# Sheet2-PICO-IMU_V2.net
KiCad netlist of a schematic drawn in Altium Designer
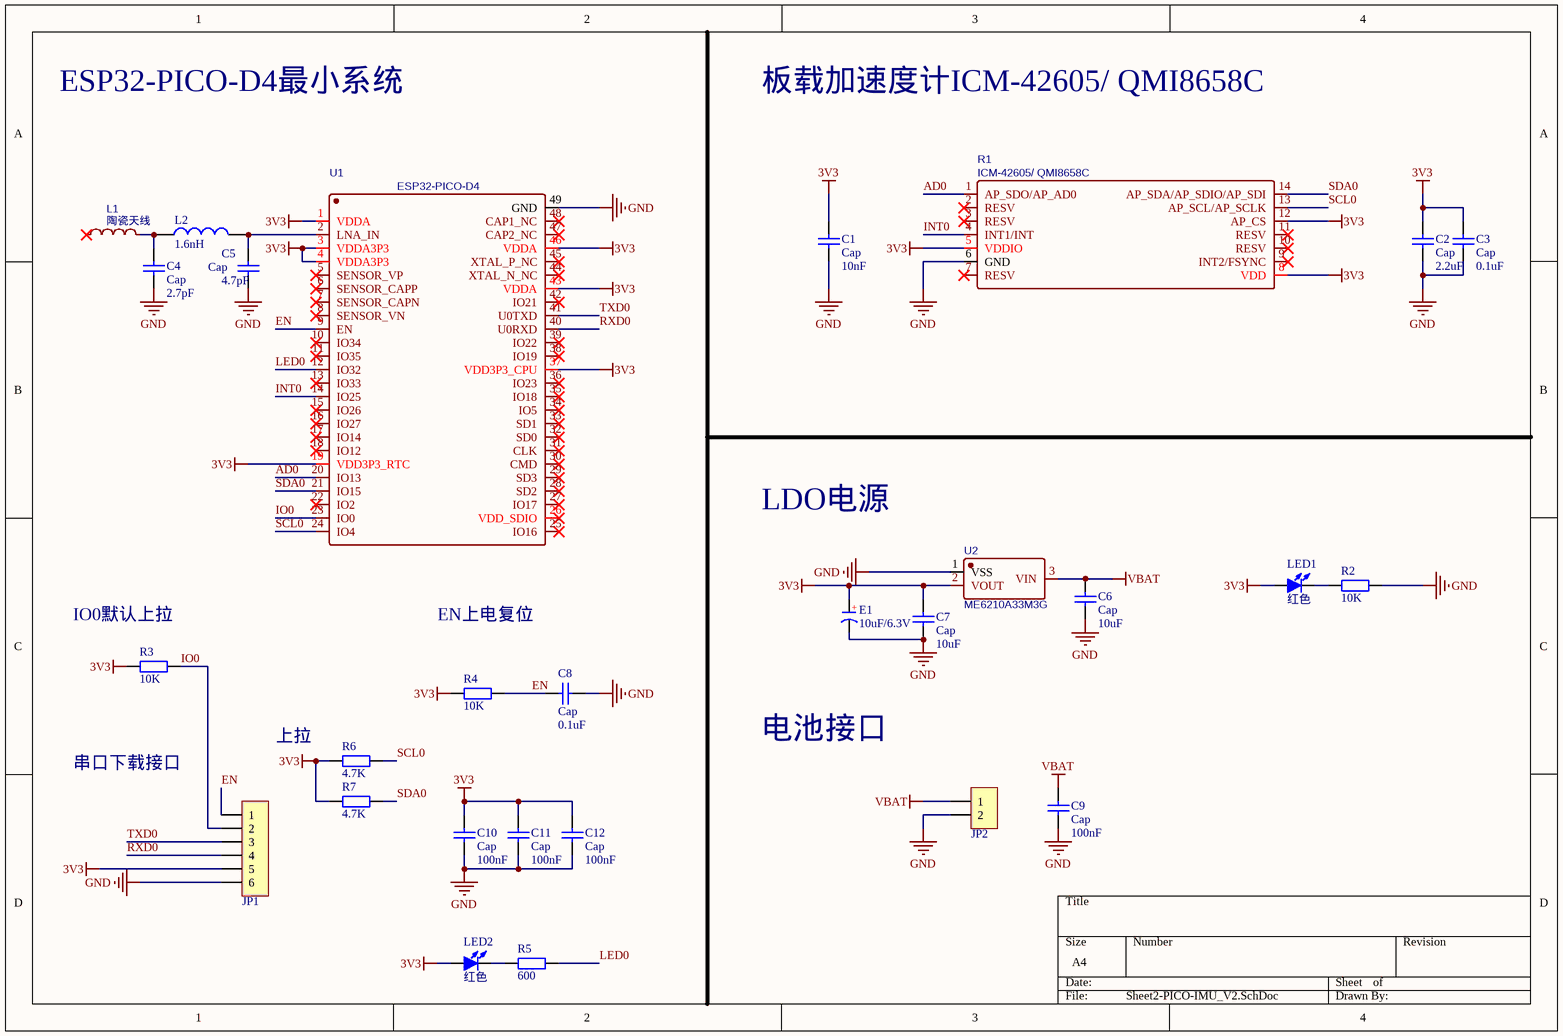
[diagram p0: Sheet2-PICO-IMU_V2.SchDoc]

(export (version "E")
  (design (tool "Eeschema 10.0.6"))
  (components
    (comp (ref "C1")
      (value "Cap")
      (footprint "C 0402_L")
      (description "Capacitor")
      (fields (field (name "ALTIUM_VALUE") "10nF") (field (name "PUBLISHER") "Altium Limited"))
      (libsource (lib "Miscellaneous Devices") (part "Cap"))
    )
    (comp (ref "C2")
      (value "Cap")
      (footprint "C 0402_L")
      (description "Capacitor")
      (fields (field (name "ALTIUM_VALUE") "2.2uF") (field (name "PUBLISHER") "Altium Limited"))
      (libsource (lib "Miscellaneous Devices") (part "Cap"))
    )
    (comp (ref "C3")
      (value "Cap")
      (footprint "C 0402_L")
      (description "Capacitor")
      (fields (field (name "ALTIUM_VALUE") "0.1uF") (field (name "PUBLISHER") "Altium Limited"))
      (libsource (lib "Miscellaneous Devices") (part "Cap"))
    )
    (comp (ref "C4")
      (value "Cap")
      (footprint "C 0402_L")
      (description "Capacitor")
      (fields (field (name "ALTIUM_VALUE") "2.7pF") (field (name "PUBLISHER") "Altium Limited"))
      (libsource (lib "Miscellaneous Devices") (part "Cap"))
    )
    (comp (ref "C5")
      (value "Cap")
      (footprint "C 0402_L")
      (description "Capacitor")
      (fields (field (name "ALTIUM_VALUE") "4.7pF") (field (name "PUBLISHER") "Altium Limited"))
      (libsource (lib "Miscellaneous Devices") (part "Cap"))
    )
    (comp (ref "C6")
      (value "Cap")
      (footprint "C 0402_L")
      (description "Capacitor")
      (fields (field (name "ALTIUM_VALUE") "10uF") (field (name "PUBLISHER") "Altium Limited"))
      (libsource (lib "Miscellaneous Devices") (part "Cap"))
    )
    (comp (ref "C7")
      (value "Cap")
      (footprint "C 0402_L")
      (description "Capacitor")
      (fields (field (name "ALTIUM_VALUE") "10uF") (field (name "PUBLISHER") "Altium Limited"))
      (libsource (lib "Miscellaneous Devices") (part "Cap"))
    )
    (comp (ref "C8")
      (value "Cap")
      (footprint "C 0402_L")
      (description "Capacitor")
      (fields (field (name "ALTIUM_VALUE") "0.1uF") (field (name "PUBLISHER") "Altium Limited"))
      (libsource (lib "Miscellaneous Devices") (part "Cap"))
    )
    (comp (ref "C9")
      (value "Cap")
      (footprint "C 0402_L")
      (description "Capacitor")
      (fields (field (name "ALTIUM_VALUE") "100nF") (field (name "PUBLISHER") "Altium Limited"))
      (libsource (lib "Miscellaneous Devices") (part "Cap"))
    )
    (comp (ref "C10")
      (value "Cap")
      (footprint "C 0402_L")
      (description "Capacitor")
      (fields (field (name "ALTIUM_VALUE") "100nF") (field (name "PUBLISHER") "Altium Limited"))
      (libsource (lib "Miscellaneous Devices") (part "Cap"))
    )
    (comp (ref "C11")
      (value "Cap")
      (footprint "C 0402_L")
      (description "Capacitor")
      (fields (field (name "ALTIUM_VALUE") "100nF") (field (name "PUBLISHER") "Altium Limited"))
      (libsource (lib "Miscellaneous Devices") (part "Cap"))
    )
    (comp (ref "C12")
      (value "Cap")
      (footprint "C 0402_L")
      (description "Capacitor")
      (fields (field (name "ALTIUM_VALUE") "100nF") (field (name "PUBLISHER") "Altium Limited"))
      (libsource (lib "Miscellaneous Devices") (part "Cap"))
    )
    (comp (ref "E1")
      (value "10uF/6.3V")
      (footprint "CD S(2012)")
      (description "贴片钽电容")
      (fields (field (name "版权归属") "源创客"))
      (libsource (lib "Basic_Integrated_Library") (part "C-CD"))
    )
    (comp (ref "JP1")
      (value "HDR-1X6")
      (footprint "debug")
      (description "6P接插件")
      (fields (field (name "版权归属") "源创客"))
      (libsource (lib "Basic_Integrated_Library") (part "Header 6"))
    )
    (comp (ref "JP2")
      (value "HDR-1X2")
      (footprint "电池焊接口")
      (description "2P接插件")
      (fields (field (name "版权归属") "源创客"))
      (libsource (lib "Basic_Integrated_Library") (part "Header 2"))
    )
    (comp (ref "L1")
      (value "陶瓷天线")
      (footprint "Huaxin")
      (fields
        (field (name "BOM_SUPPLIER PART") "C127620")
        (field (name "BOM_MANUFACTURER PART") "RFECA3216060A1T")
        (field (name "CONTRIBUTOR") "LCSC")
      )
      (libsource (lib "altium-import") (part "root_0_Huaxin_"))
    )
    (comp (ref "L2")
      (value "1.6nH")
      (footprint "L 0402")
      (description "小功率贴片电感")
      (fields (field (name "版权归属") "源创客"))
      (libsource (lib "Basic_Integrated_Library") (part "L"))
    )
    (comp (ref "LED1")
      (value "红色")
      (footprint "LED 0805G")
      (description "贴片LED")
      (fields (field (name "版权归属") "源创客"))
      (libsource (lib "Basic_Integrated_Library") (part "LED-SMD"))
    )
    (comp (ref "LED2")
      (value "红色")
      (footprint "LED 0805G")
      (description "贴片LED")
      (fields (field (name "版权归属") "源创客"))
      (libsource (lib "Basic_Integrated_Library") (part "LED-SMD"))
    )
    (comp (ref "R1")
      (value "ICM-42605/ QMI8658C")
      (footprint "ICM-42605")
      (fields
        (field (name "BOM_SUPPLIER PART") "C2655099")
        (field (name "BOM_MANUFACTURER PART") "ICM-42605")
        (field (name "CONTRIBUTOR") "LCSC")
      )
      (libsource (lib "altium-import") (part "root_0_ICM-42605_"))
    )
    (comp (ref "R2")
      (value "10K")
      (footprint "R 0402_L")
      (description "贴片电阻")
      (fields (field (name "版权归属") "源创客"))
      (libsource (lib "Basic_Integrated_Library") (part "R"))
    )
    (comp (ref "R3")
      (value "10K")
      (footprint "R 0402_L")
      (description "贴片电阻")
      (fields (field (name "版权归属") "源创客"))
      (libsource (lib "Basic_Integrated_Library") (part "R"))
    )
    (comp (ref "R4")
      (value "10K")
      (footprint "R 0402_L")
      (description "贴片电阻")
      (fields (field (name "版权归属") "源创客"))
      (libsource (lib "Basic_Integrated_Library") (part "R"))
    )
    (comp (ref "R5")
      (value "600")
      (footprint "R 0402_L")
      (description "贴片电阻")
      (fields (field (name "版权归属") "源创客"))
      (libsource (lib "Basic_Integrated_Library") (part "R"))
    )
    (comp (ref "R6")
      (value "4.7K")
      (footprint "R 0402_L")
      (description "贴片电阻")
      (fields (field (name "版权归属") "源创客"))
      (libsource (lib "Basic_Integrated_Library") (part "R"))
    )
    (comp (ref "R7")
      (value "4.7K")
      (footprint "R 0402_L")
      (description "贴片电阻")
      (fields (field (name "版权归属") "源创客"))
      (libsource (lib "Basic_Integrated_Library") (part "R"))
    )
    (comp (ref "U1")
      (value "ESP32-PICO-D4")
      (footprint "ESP32-PICO-D4")
      (fields (field (name "BOM_SUPPLIER PART") "C193707") (field (name "CONTRIBUTOR") "LCSC"))
      (libsource (lib "altium-import") (part "root_0_ESP32-PICO-D4_"))
    )
    (comp (ref "U2")
      (value "ME6210A33M3G")
      (footprint "ME6210A33M3G")
      (fields (field (name "BOM_SUPPLIER PART") "C236680") (field (name "CONTRIBUTOR") "LCSC"))
      (libsource (lib "altium-import") (part "root_0_ME6210A33M3G_"))
    )
  )
  (nets
    (net (code "1") (name "/AD0") (class "Default")
      (node (ref "R1") (pin "1") (pinfunction "AP_SDO/AP_AD0_1") (pintype "passive"))
      (node (ref "U1") (pin "20") (pinfunction "IO13_20") (pintype "passive"))
    )
    (net (code "2") (name "/EN") (class "Default")
      (node (ref "C8") (pin "2") (pinfunction "2_2") (pintype "passive"))
      (node (ref "JP1") (pin "1") (pinfunction "1_1") (pintype "passive"))
      (node (ref "R4") (pin "2") (pinfunction "2_2") (pintype "passive"))
      (node (ref "U1") (pin "9") (pinfunction "EN_9") (pintype "passive"))
    )
    (net (code "3") (name "/INT0") (class "Default")
      (node (ref "R1") (pin "4") (pinfunction "INT1/INT_4") (pintype "passive"))
      (node (ref "U1") (pin "14") (pinfunction "IO25_14") (pintype "passive"))
    )
    (net (code "4") (name "/IO0") (class "Default")
      (node (ref "JP1") (pin "2") (pinfunction "2_2") (pintype "passive"))
      (node (ref "R3") (pin "2") (pinfunction "2_2") (pintype "passive"))
      (node (ref "U1") (pin "23") (pinfunction "IO0_23") (pintype "passive"))
    )
    (net (code "5") (name "/LED0") (class "Default")
      (node (ref "R5") (pin "2") (pinfunction "2_2") (pintype "passive"))
      (node (ref "U1") (pin "12") (pinfunction "IO32_12") (pintype "passive"))
    )
    (net (code "6") (name "/RXD0") (class "Default")
      (node (ref "JP1") (pin "4") (pinfunction "4_4") (pintype "passive"))
      (node (ref "U1") (pin "40") (pinfunction "U0RXD_40") (pintype "passive"))
    )
    (net (code "7") (name "/SCL0") (class "Default")
      (node (ref "R1") (pin "13") (pinfunction "AP_SCL/AP_SCLK_13") (pintype "passive"))
      (node (ref "R6") (pin "2") (pinfunction "2_2") (pintype "passive"))
      (node (ref "U1") (pin "24") (pinfunction "IO4_24") (pintype "passive"))
    )
    (net (code "8") (name "/SDA0") (class "Default")
      (node (ref "R1") (pin "14") (pinfunction "AP_SDA/AP_SDIO/AP_SDI_14") (pintype "passive"))
      (node (ref "R7") (pin "2") (pinfunction "2_2") (pintype "passive"))
      (node (ref "U1") (pin "21") (pinfunction "IO15_21") (pintype "passive"))
    )
    (net (code "9") (name "/TXD0") (class "Default")
      (node (ref "JP1") (pin "3") (pinfunction "3_3") (pintype "passive"))
      (node (ref "U1") (pin "41") (pinfunction "U0TXD_41") (pintype "passive"))
    )
    (net (code "10") (name "3V3") (class "Default")
      (node (ref "C1") (pin "2") (pinfunction "2_2") (pintype "passive"))
      (node (ref "C10") (pin "1") (pinfunction "1_1") (pintype "passive"))
      (node (ref "C11") (pin "1") (pinfunction "1_1") (pintype "passive"))
      (node (ref "C12") (pin "1") (pinfunction "1_1") (pintype "passive"))
      (node (ref "C2") (pin "2") (pinfunction "2_2") (pintype "passive"))
      (node (ref "C3") (pin "2") (pinfunction "2_2") (pintype "passive"))
      (node (ref "C7") (pin "2") (pinfunction "2_2") (pintype "passive"))
      (node (ref "E1") (pin "1") (pinfunction "A_1") (pintype "passive"))
      (node (ref "JP1") (pin "5") (pinfunction "5_5") (pintype "passive"))
      (node (ref "LED1") (pin "1") (pinfunction "A_1") (pintype "passive"))
      (node (ref "LED2") (pin "1") (pinfunction "A_1") (pintype "passive"))
      (node (ref "R1") (pin "12") (pinfunction "AP_CS_12") (pintype "passive"))
      (node (ref "R1") (pin "5") (pinfunction "VDDIO_5") (pintype "passive"))
      (node (ref "R1") (pin "8") (pinfunction "VDD_8") (pintype "passive"))
      (node (ref "R3") (pin "1") (pinfunction "1_1") (pintype "passive"))
      (node (ref "R4") (pin "1") (pinfunction "1_1") (pintype "passive"))
      (node (ref "R6") (pin "1") (pinfunction "1_1") (pintype "passive"))
      (node (ref "R7") (pin "1") (pinfunction "1_1") (pintype "passive"))
      (node (ref "U1") (pin "1") (pinfunction "VDDA_1") (pintype "passive"))
      (node (ref "U1") (pin "19") (pinfunction "VDD3P3_RTC_19") (pintype "passive"))
      (node (ref "U1") (pin "3") (pinfunction "VDDA3P3_3") (pintype "passive"))
      (node (ref "U1") (pin "37") (pinfunction "VDD3P3_CPU_37") (pintype "passive"))
      (node (ref "U1") (pin "4") (pinfunction "VDDA3P3_4") (pintype "passive"))
      (node (ref "U1") (pin "43") (pinfunction "VDDA_43") (pintype "passive"))
      (node (ref "U1") (pin "46") (pinfunction "VDDA_46") (pintype "passive"))
      (node (ref "U2") (pin "2") (pinfunction "VOUT_2") (pintype "passive"))
    )
    (net (code "11") (name "GND") (class "Default")
      (node (ref "C1") (pin "1") (pinfunction "1_1") (pintype "passive"))
      (node (ref "C10") (pin "2") (pinfunction "2_2") (pintype "passive"))
      (node (ref "C11") (pin "2") (pinfunction "2_2") (pintype "passive"))
      (node (ref "C12") (pin "2") (pinfunction "2_2") (pintype "passive"))
      (node (ref "C2") (pin "1") (pinfunction "1_1") (pintype "passive"))
      (node (ref "C3") (pin "1") (pinfunction "1_1") (pintype "passive"))
      (node (ref "C4") (pin "2") (pinfunction "2_2") (pintype "passive"))
      (node (ref "C5") (pin "2") (pinfunction "2_2") (pintype "passive"))
      (node (ref "C6") (pin "1") (pinfunction "1_1") (pintype "passive"))
      (node (ref "C7") (pin "1") (pinfunction "1_1") (pintype "passive"))
      (node (ref "C8") (pin "1") (pinfunction "1_1") (pintype "passive"))
      (node (ref "C9") (pin "1") (pinfunction "1_1") (pintype "passive"))
      (node (ref "E1") (pin "2") (pinfunction "K_2") (pintype "passive"))
      (node (ref "JP1") (pin "6") (pinfunction "6_6") (pintype "passive"))
      (node (ref "JP2") (pin "2") (pinfunction "2_2") (pintype "passive"))
      (node (ref "R1") (pin "6") (pinfunction "GND_6") (pintype "passive"))
      (node (ref "R2") (pin "2") (pinfunction "2_2") (pintype "passive"))
      (node (ref "U1") (pin "49") (pinfunction "GND_49") (pintype "passive"))
      (node (ref "U2") (pin "1") (pinfunction "VSS_1") (pintype "passive"))
    )
    (net (code "12") (name "Net-(C4-Pad1)") (class "Default")
      (node (ref "C4") (pin "1") (pinfunction "1_1") (pintype "passive"))
      (node (ref "L1") (pin "2") (pinfunction "2_2") (pintype "passive"))
      (node (ref "L2") (pin "1") (pinfunction "1_1") (pintype "passive"))
    )
    (net (code "13") (name "Net-(LED1-K)") (class "Default")
      (node (ref "LED1") (pin "2") (pinfunction "K_2") (pintype "passive"))
      (node (ref "R2") (pin "1") (pinfunction "1_1") (pintype "passive"))
    )
    (net (code "14") (name "Net-(LED2-K)") (class "Default")
      (node (ref "LED2") (pin "2") (pinfunction "K_2") (pintype "passive"))
      (node (ref "R5") (pin "1") (pinfunction "1_1") (pintype "passive"))
    )
    (net (code "15") (name "Net-(U1-LNA_IN)") (class "Default")
      (node (ref "C5") (pin "1") (pinfunction "1_1") (pintype "passive"))
      (node (ref "L2") (pin "2") (pinfunction "2_2") (pintype "passive"))
      (node (ref "U1") (pin "2") (pinfunction "LNA_IN_2") (pintype "passive"))
    )
    (net (code "16") (name "VBAT") (class "Default")
      (node (ref "C6") (pin "2") (pinfunction "2_2") (pintype "passive"))
      (node (ref "C9") (pin "2") (pinfunction "2_2") (pintype "passive"))
      (node (ref "JP2") (pin "1") (pinfunction "1_1") (pintype "passive"))
      (node (ref "U2") (pin "3") (pinfunction "VIN_3") (pintype "passive"))
    )
    (net (code "17") (name "unconnected-(L1-Pad1)") (class "Default")
      (node (ref "L1") (pin "1") (pinfunction "1_1") (pintype "passive+no_connect"))
    )
    (net (code "18") (name "unconnected-(R1-INT2{slash}FSYNC-Pad9)") (class "Default")
      (node (ref "R1") (pin "9") (pinfunction "INT2/FSYNC_9") (pintype "passive+no_connect"))
    )
    (net (code "19") (name "unconnected-(R1-RESV-Pad2)") (class "Default")
      (node (ref "R1") (pin "2") (pinfunction "RESV_2") (pintype "passive+no_connect"))
    )
    (net (code "20") (name "unconnected-(R1-RESV-Pad3)") (class "Default")
      (node (ref "R1") (pin "3") (pinfunction "RESV_3") (pintype "passive+no_connect"))
    )
    (net (code "21") (name "unconnected-(R1-RESV-Pad7)") (class "Default")
      (node (ref "R1") (pin "7") (pinfunction "RESV_7") (pintype "passive+no_connect"))
    )
    (net (code "22") (name "unconnected-(R1-RESV-Pad10)") (class "Default")
      (node (ref "R1") (pin "10") (pinfunction "RESV_10") (pintype "passive+no_connect"))
    )
    (net (code "23") (name "unconnected-(R1-RESV-Pad11)") (class "Default")
      (node (ref "R1") (pin "11") (pinfunction "RESV_11") (pintype "passive+no_connect"))
    )
    (net (code "24") (name "unconnected-(U1-CAP1_NC-Pad48)") (class "Default")
      (node (ref "U1") (pin "48") (pinfunction "CAP1_NC_48") (pintype "passive+no_connect"))
    )
    (net (code "25") (name "unconnected-(U1-CAP2_NC-Pad47)") (class "Default")
      (node (ref "U1") (pin "47") (pinfunction "CAP2_NC_47") (pintype "passive+no_connect"))
    )
    (net (code "26") (name "unconnected-(U1-CLK-Pad31)") (class "Default")
      (node (ref "U1") (pin "31") (pinfunction "CLK_31") (pintype "passive+no_connect"))
    )
    (net (code "27") (name "unconnected-(U1-CMD-Pad30)") (class "Default")
      (node (ref "U1") (pin "30") (pinfunction "CMD_30") (pintype "passive+no_connect"))
    )
    (net (code "28") (name "unconnected-(U1-IO2-Pad22)") (class "Default")
      (node (ref "U1") (pin "22") (pinfunction "IO2_22") (pintype "passive+no_connect"))
    )
    (net (code "29") (name "unconnected-(U1-IO5-Pad34)") (class "Default")
      (node (ref "U1") (pin "34") (pinfunction "IO5_34") (pintype "passive+no_connect"))
    )
    (net (code "30") (name "unconnected-(U1-IO12-Pad18)") (class "Default")
      (node (ref "U1") (pin "18") (pinfunction "IO12_18") (pintype "passive+no_connect"))
    )
    (net (code "31") (name "unconnected-(U1-IO14-Pad17)") (class "Default")
      (node (ref "U1") (pin "17") (pinfunction "IO14_17") (pintype "passive+no_connect"))
    )
    (net (code "32") (name "unconnected-(U1-IO16-Pad25)") (class "Default")
      (node (ref "U1") (pin "25") (pinfunction "IO16_25") (pintype "passive+no_connect"))
    )
    (net (code "33") (name "unconnected-(U1-IO17-Pad27)") (class "Default")
      (node (ref "U1") (pin "27") (pinfunction "IO17_27") (pintype "passive+no_connect"))
    )
    (net (code "34") (name "unconnected-(U1-IO18-Pad35)") (class "Default")
      (node (ref "U1") (pin "35") (pinfunction "IO18_35") (pintype "passive+no_connect"))
    )
    (net (code "35") (name "unconnected-(U1-IO19-Pad38)") (class "Default")
      (node (ref "U1") (pin "38") (pinfunction "IO19_38") (pintype "passive+no_connect"))
    )
    (net (code "36") (name "unconnected-(U1-IO21-Pad42)") (class "Default")
      (node (ref "U1") (pin "42") (pinfunction "IO21_42") (pintype "passive+no_connect"))
    )
    (net (code "37") (name "unconnected-(U1-IO22-Pad39)") (class "Default")
      (node (ref "U1") (pin "39") (pinfunction "IO22_39") (pintype "passive+no_connect"))
    )
    (net (code "38") (name "unconnected-(U1-IO23-Pad36)") (class "Default")
      (node (ref "U1") (pin "36") (pinfunction "IO23_36") (pintype "passive+no_connect"))
    )
    (net (code "39") (name "unconnected-(U1-IO26-Pad15)") (class "Default")
      (node (ref "U1") (pin "15") (pinfunction "IO26_15") (pintype "passive+no_connect"))
    )
    (net (code "40") (name "unconnected-(U1-IO27-Pad16)") (class "Default")
      (node (ref "U1") (pin "16") (pinfunction "IO27_16") (pintype "passive+no_connect"))
    )
    (net (code "41") (name "unconnected-(U1-IO33-Pad13)") (class "Default")
      (node (ref "U1") (pin "13") (pinfunction "IO33_13") (pintype "passive+no_connect"))
    )
    (net (code "42") (name "unconnected-(U1-IO34-Pad10)") (class "Default")
      (node (ref "U1") (pin "10") (pinfunction "IO34_10") (pintype "passive+no_connect"))
    )
    (net (code "43") (name "unconnected-(U1-IO35-Pad11)") (class "Default")
      (node (ref "U1") (pin "11") (pinfunction "IO35_11") (pintype "passive+no_connect"))
    )
    (net (code "44") (name "unconnected-(U1-SD0-Pad32)") (class "Default")
      (node (ref "U1") (pin "32") (pinfunction "SD0_32") (pintype "passive+no_connect"))
    )
    (net (code "45") (name "unconnected-(U1-SD1-Pad33)") (class "Default")
      (node (ref "U1") (pin "33") (pinfunction "SD1_33") (pintype "passive+no_connect"))
    )
    (net (code "46") (name "unconnected-(U1-SD2-Pad28)") (class "Default")
      (node (ref "U1") (pin "28") (pinfunction "SD2_28") (pintype "passive+no_connect"))
    )
    (net (code "47") (name "unconnected-(U1-SD3-Pad29)") (class "Default")
      (node (ref "U1") (pin "29") (pinfunction "SD3_29") (pintype "passive+no_connect"))
    )
    (net (code "48") (name "unconnected-(U1-SENSOR_CAPN-Pad7)") (class "Default")
      (node (ref "U1") (pin "7") (pinfunction "SENSOR_CAPN_7") (pintype "passive+no_connect"))
    )
    (net (code "49") (name "unconnected-(U1-SENSOR_CAPP-Pad6)") (class "Default")
      (node (ref "U1") (pin "6") (pinfunction "SENSOR_CAPP_6") (pintype "passive+no_connect"))
    )
    (net (code "50") (name "unconnected-(U1-SENSOR_VN-Pad8)") (class "Default")
      (node (ref "U1") (pin "8") (pinfunction "SENSOR_VN_8") (pintype "passive+no_connect"))
    )
    (net (code "51") (name "unconnected-(U1-SENSOR_VP-Pad5)") (class "Default")
      (node (ref "U1") (pin "5") (pinfunction "SENSOR_VP_5") (pintype "passive+no_connect"))
    )
    (net (code "52") (name "unconnected-(U1-VDD_SDIO-Pad26)") (class "Default")
      (node (ref "U1") (pin "26") (pinfunction "VDD_SDIO_26") (pintype "passive+no_connect"))
    )
    (net (code "53") (name "unconnected-(U1-XTAL_N_NC-Pad44)") (class "Default")
      (node (ref "U1") (pin "44") (pinfunction "XTAL_N_NC_44") (pintype "passive+no_connect"))
    )
    (net (code "54") (name "unconnected-(U1-XTAL_P_NC-Pad45)") (class "Default")
      (node (ref "U1") (pin "45") (pinfunction "XTAL_P_NC_45") (pintype "passive+no_connect"))
    )
  )
)
